# i2c_adc_avr_inline.net
KiCad netlist of a schematic drawn in EAGLE
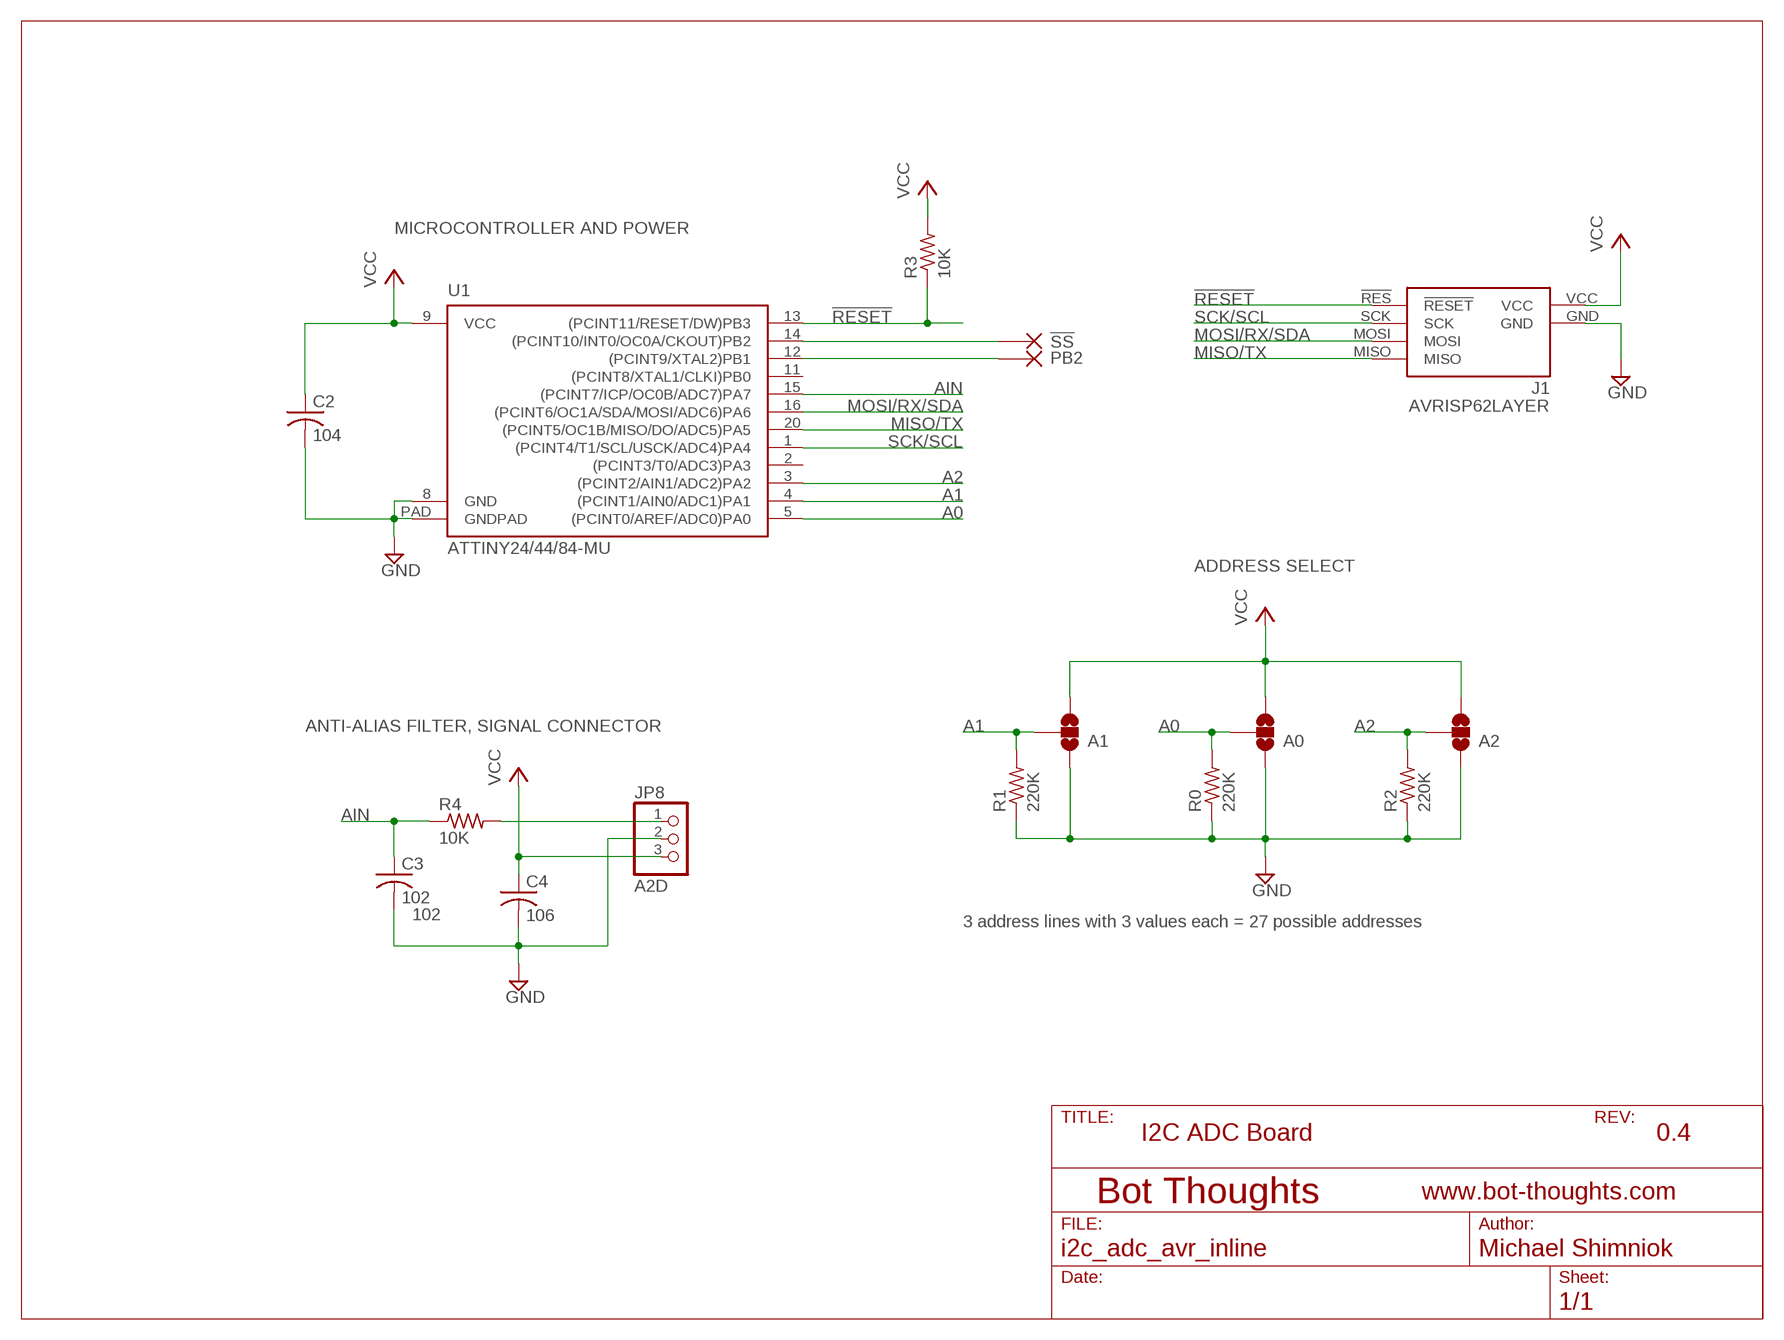
[diagram p0: schematic, sheet 1]

(export (version "E")
  (design (tool "Eeschema 10.0.6"))
  (components
    (comp (ref "A0")
      (value "SOLDERJUMPER_2WAYS")
      (footprint "eagle-import:SJ_3")
      (libsource (lib "eagle-import") (part "SOLDERJUMPER_2WAYS"))
    )
    (comp (ref "A1")
      (value "SOLDERJUMPER_2WAYS")
      (footprint "eagle-import:SJ_3")
      (libsource (lib "eagle-import") (part "SOLDERJUMPER_2WAYS"))
    )
    (comp (ref "A2")
      (value "SOLDERJUMPER_2WAYS")
      (footprint "eagle-import:SJ_3")
      (libsource (lib "eagle-import") (part "SOLDERJUMPER_2WAYS"))
    )
    (comp (ref "C2")
      (value "104")
      (footprint "eagle-import:C0603")
      (fields (field (name "PARTNO") "C1608X7R1E104K080AA"))
      (libsource (lib "eagle-import") (part "C-USC0603"))
    )
    (comp (ref "C3")
      (value "102")
      (footprint "eagle-import:C0603")
      (fields (field (name "CODE") "102") (field (name "PARTNO") "CL10B102KB8SFNC"))
      (libsource (lib "eagle-import") (part "C-USC0603"))
    )
    (comp (ref "C4")
      (value "106")
      (footprint "eagle-import:C0603")
      (fields (field (name "PARTNO") "CL10A106MP8NNNC"))
      (libsource (lib "eagle-import") (part "C-USC0603"))
    )
    (comp (ref "J1")
      (value "AVRISP62LAYER")
      (footprint "eagle-import:2X3_2LAYER")
      (libsource (lib "eagle-import") (part "AVRISP62LAYER"))
    )
    (comp (ref "JP8")
      (value "A2D")
      (footprint "eagle-import:1X03-S")
      (libsource (lib "eagle-import") (part "PINHD-1X03_2.54-S"))
    )
    (comp (ref "R0")
      (value "220K")
      (footprint "eagle-import:R0603")
      (fields (field (name "PARTNO") "RC1608J224CS"))
      (libsource (lib "eagle-import") (part "R-US_R0603"))
    )
    (comp (ref "R1")
      (value "220K")
      (footprint "eagle-import:R0603")
      (fields (field (name "PARTNO") "RC1608J224CS"))
      (libsource (lib "eagle-import") (part "R-US_R0603"))
    )
    (comp (ref "R2")
      (value "220K")
      (footprint "eagle-import:R0603")
      (fields (field (name "PARTNO") "RC1608J224CS"))
      (libsource (lib "eagle-import") (part "R-US_R0603"))
    )
    (comp (ref "R3")
      (value "10K")
      (footprint "eagle-import:R0603")
      (fields (field (name "PARTNO") "1622829-1"))
      (libsource (lib "eagle-import") (part "R-US_R0603"))
    )
    (comp (ref "R4")
      (value "10K")
      (footprint "eagle-import:R0603")
      (fields (field (name "PARTNO") "1622829-1"))
      (libsource (lib "eagle-import") (part "R-US_R0603"))
    )
    (comp (ref "U1")
      (value "ATTINY24/44/84-MU")
      (footprint "eagle-import:20MLF_0.5")
      (libsource (lib "eagle-import") (part "ATTINY24/44/84-MU"))
    )
    (comp (ref "X1")
      (value "!SS")
      (footprint "eagle-import:PAD0.07X0.15")
      (libsource (lib "eagle-import") (part "PINPADSMD0.07X0.15"))
    )
    (comp (ref "X4")
      (value "PB2")
      (footprint "eagle-import:PAD0.07X0.15")
      (libsource (lib "eagle-import") (part "PINPADSMD0.07X0.15"))
    )
  )
  (nets
    (net (code "1") (name "/A0") (class "Default")
      (node (ref "A0") (pin "2") (pinfunction "2_2") (pintype "passive"))
      (node (ref "R0") (pin "2") (pinfunction "2_2") (pintype "passive"))
      (node (ref "U1") (pin "5") (pinfunction "(PCINT0/AREF/ADC0)PA0_5") (pintype "bidirectional"))
    )
    (net (code "2") (name "/A1") (class "Default")
      (node (ref "A1") (pin "2") (pinfunction "2_2") (pintype "passive"))
      (node (ref "R1") (pin "2") (pinfunction "2_2") (pintype "passive"))
      (node (ref "U1") (pin "4") (pinfunction "(PCINT1/AIN0/ADC1)PA1_4") (pintype "bidirectional"))
    )
    (net (code "3") (name "/A2") (class "Default")
      (node (ref "A2") (pin "2") (pinfunction "2_2") (pintype "passive"))
      (node (ref "R2") (pin "2") (pinfunction "2_2") (pintype "passive"))
      (node (ref "U1") (pin "3") (pinfunction "(PCINT2/AIN1/ADC2)PA2_3") (pintype "bidirectional"))
    )
    (net (code "4") (name "/AIN") (class "Default")
      (node (ref "C3") (pin "1") (pinfunction "1_1") (pintype "passive"))
      (node (ref "R4") (pin "1") (pinfunction "1_1") (pintype "passive"))
      (node (ref "U1") (pin "15") (pinfunction "(PCINT7/ICP/OC0B/ADC7)PA7_15") (pintype "bidirectional"))
    )
    (net (code "5") (name "/MISO{slash}TX") (class "Default")
      (node (ref "J1") (pin "MISO") (pinfunction "MISO_MISO") (pintype "input"))
      (node (ref "U1") (pin "20") (pinfunction "(PCINT5/OC1B/MISO/DO/ADC5)PA5_20") (pintype "bidirectional"))
    )
    (net (code "6") (name "/MOSI{slash}RX{slash}SDA") (class "Default")
      (node (ref "J1") (pin "MOSI") (pinfunction "MOSI_MOSI") (pintype "output"))
      (node (ref "U1") (pin "16") (pinfunction "(PCINT6/OC1A/SDA/MOSI/ADC6)PA6_16") (pintype "bidirectional"))
    )
    (net (code "7") (name "/SCK{slash}SCL") (class "Default")
      (node (ref "J1") (pin "SCK") (pinfunction "SCK_SCK") (pintype "output"))
      (node (ref "U1") (pin "1") (pinfunction "(PCINT4/T1/SCL/USCK/ADC4)PA4_1") (pintype "bidirectional"))
    )
    (net (code "8") (name "/~{RESET}") (class "Default")
      (node (ref "J1") (pin "!RES") (pinfunction "~{RESET}_!RES") (pintype "output"))
      (node (ref "R3") (pin "1") (pinfunction "1_1") (pintype "passive"))
      (node (ref "U1") (pin "13") (pinfunction "(PCINT11/RESET/DW)PB3_13") (pintype "bidirectional"))
    )
    (net (code "9") (name "GND") (class "Default")
      (node (ref "A0") (pin "1") (pinfunction "1_1") (pintype "passive"))
      (node (ref "A1") (pin "1") (pinfunction "1_1") (pintype "passive"))
      (node (ref "A2") (pin "1") (pinfunction "1_1") (pintype "passive"))
      (node (ref "C2") (pin "2") (pinfunction "2_2") (pintype "passive"))
      (node (ref "C3") (pin "2") (pinfunction "2_2") (pintype "passive"))
      (node (ref "C4") (pin "2") (pinfunction "2_2") (pintype "passive"))
      (node (ref "J1") (pin "GND") (pinfunction "GND_GND") (pintype "power_in"))
      (node (ref "JP8") (pin "2") (pinfunction "2_2") (pintype "passive"))
      (node (ref "R0") (pin "1") (pinfunction "1_1") (pintype "passive"))
      (node (ref "R1") (pin "1") (pinfunction "1_1") (pintype "passive"))
      (node (ref "R2") (pin "1") (pinfunction "1_1") (pintype "passive"))
      (node (ref "U1") (pin "8") (pinfunction "GND_8") (pintype "bidirectional"))
      (node (ref "U1") (pin "PAD") (pinfunction "GNDPAD_PAD") (pintype "bidirectional"))
    )
    (net (code "10") (name "Net-(JP8-Pad1)") (class "Default")
      (node (ref "JP8") (pin "1") (pinfunction "1_1") (pintype "passive"))
      (node (ref "R4") (pin "2") (pinfunction "2_2") (pintype "passive"))
    )
    (net (code "11") (name "Net-(U1-(PCINT9{slash}XTAL2)PB1)") (class "Default")
      (node (ref "U1") (pin "12") (pinfunction "(PCINT9/XTAL2)PB1_12") (pintype "bidirectional"))
      (node (ref "X4") (pin "P$1") (pinfunction "P$1_P$1") (pintype "bidirectional"))
    )
    (net (code "12") (name "Net-(U1-(PCINT10{slash}INT0{slash}OC0A{slash}CKOUT)PB2)") (class "Default")
      (node (ref "U1") (pin "14") (pinfunction "(PCINT10/INT0/OC0A/CKOUT)PB2_14") (pintype "bidirectional"))
      (node (ref "X1") (pin "P$1") (pinfunction "P$1_P$1") (pintype "bidirectional"))
    )
    (net (code "13") (name "VCC") (class "Default")
      (node (ref "A0") (pin "3") (pinfunction "3_3") (pintype "passive"))
      (node (ref "A1") (pin "3") (pinfunction "3_3") (pintype "passive"))
      (node (ref "A2") (pin "3") (pinfunction "3_3") (pintype "passive"))
      (node (ref "C2") (pin "1") (pinfunction "1_1") (pintype "passive"))
      (node (ref "C4") (pin "1") (pinfunction "1_1") (pintype "passive"))
      (node (ref "J1") (pin "VCC") (pinfunction "VCC_VCC") (pintype "power_in"))
      (node (ref "JP8") (pin "3") (pinfunction "3_3") (pintype "passive"))
      (node (ref "R3") (pin "2") (pinfunction "2_2") (pintype "passive"))
      (node (ref "U1") (pin "9") (pinfunction "VCC_9") (pintype "bidirectional"))
    )
    (net (code "14") (name "unconnected-(U1-(PCINT3{slash}T0{slash}ADC3)PA3-Pad2)") (class "Default")
      (node (ref "U1") (pin "2") (pinfunction "(PCINT3/T0/ADC3)PA3_2") (pintype "bidirectional"))
    )
    (net (code "15") (name "unconnected-(U1-(PCINT8{slash}XTAL1{slash}CLKI)PB0-Pad11)") (class "Default")
      (node (ref "U1") (pin "11") (pinfunction "(PCINT8/XTAL1/CLKI)PB0_11") (pintype "bidirectional"))
    )
  )
)
